# MineralFire-0_4-OLED-inprogress.net
KiCad netlist of a schematic drawn in EAGLE
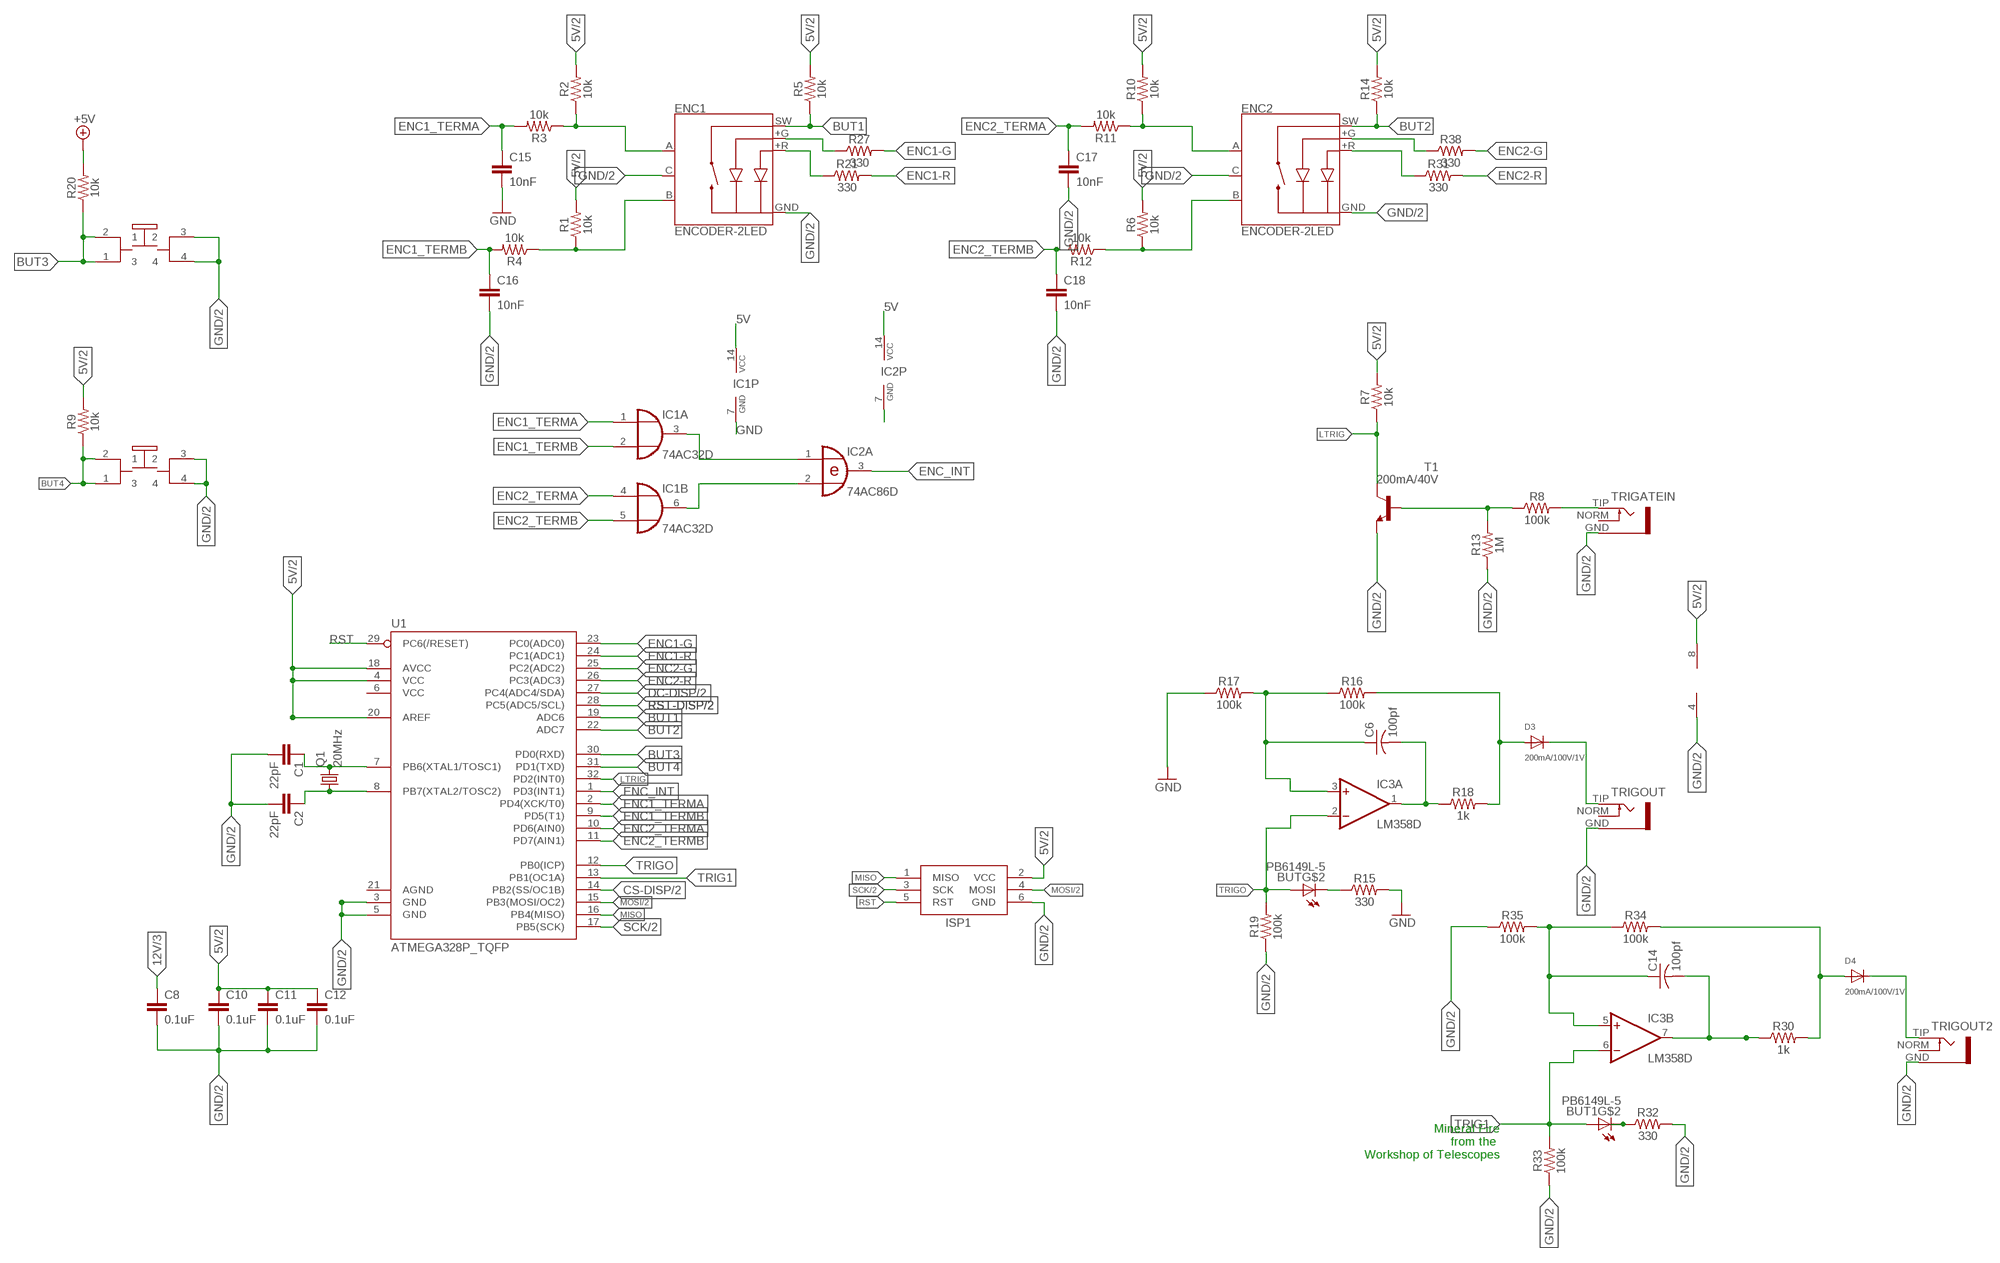
[diagram p0: schematic, sheet 1]
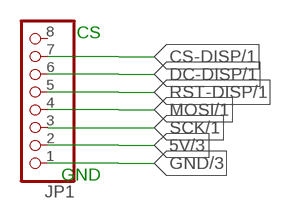
[diagram p1: schematic, sheet 2]
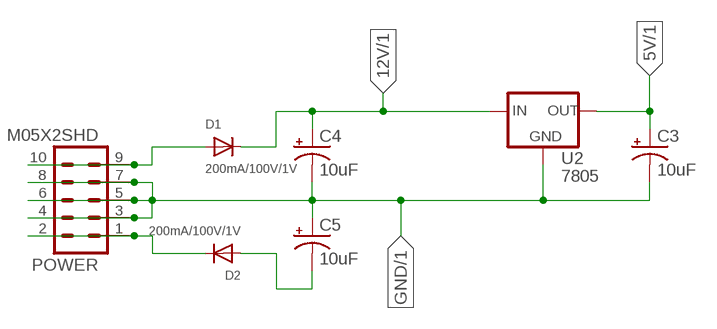
[diagram p2: schematic, sheet 3]

(export (version "E")
  (design (tool "Eeschema 10.0.6"))
  (components
    (comp (ref "BUT")
      (value "PB6149L-5")
      (footprint "eagle-import:PB6149L")
      (libsource (lib "eagle-import") (part "PB6149L-5"))
    )
    (comp (ref "BUT1")
      (value "PB6149L-5")
      (footprint "eagle-import:PB6149L")
      (libsource (lib "eagle-import") (part "PB6149L-5"))
    )
    (comp (ref "C1")
      (value "22pF")
      (footprint "eagle-import:0603")
      (libsource (lib "eagle-import") (part "22PF-0603-50V-5%"))
    )
    (comp (ref "C2")
      (value "22pF")
      (footprint "eagle-import:0603")
      (libsource (lib "eagle-import") (part "22PF-0603-50V-5%"))
    )
    (comp (ref "C6")
      (value "100pf")
      (footprint "eagle-import:C0805K")
      (libsource (lib "eagle-import") (part "C-USC0805K"))
    )
    (comp (ref "C8")
      (value "0.1uF")
      (footprint "eagle-import:0603")
      (libsource (lib "eagle-import") (part "0.1UF-0603-100V-10%"))
    )
    (comp (ref "C10")
      (value "0.1uF")
      (footprint "eagle-import:0603")
      (libsource (lib "eagle-import") (part "0.1UF-0603-100V-10%"))
    )
    (comp (ref "C11")
      (value "0.1uF")
      (footprint "eagle-import:0603")
      (libsource (lib "eagle-import") (part "0.1UF-0603-100V-10%"))
    )
    (comp (ref "C12")
      (value "0.1uF")
      (footprint "eagle-import:0603")
      (libsource (lib "eagle-import") (part "0.1UF-0603-100V-10%"))
    )
    (comp (ref "C14")
      (value "100pf")
      (footprint "eagle-import:C0805K")
      (libsource (lib "eagle-import") (part "C-USC0805K"))
    )
    (comp (ref "C15")
      (value "10nF")
      (footprint "eagle-import:0603")
      (libsource (lib "eagle-import") (part "10NF-0603-50V-10%"))
    )
    (comp (ref "C16")
      (value "10nF")
      (footprint "eagle-import:0603")
      (libsource (lib "eagle-import") (part "10NF-0603-50V-10%"))
    )
    (comp (ref "C17")
      (value "10nF")
      (footprint "eagle-import:0603")
      (libsource (lib "eagle-import") (part "10NF-0603-50V-10%"))
    )
    (comp (ref "C18")
      (value "10nF")
      (footprint "eagle-import:0603")
      (libsource (lib "eagle-import") (part "10NF-0603-50V-10%"))
    )
    (comp (ref "D3")
      (value "200mA/100V/1V")
      (footprint "eagle-import:SMADIODE")
      (libsource (lib "eagle-import") (part "DIODESMA"))
    )
    (comp (ref "D4")
      (value "200mA/100V/1V")
      (footprint "eagle-import:SMADIODE")
      (libsource (lib "eagle-import") (part "DIODESMA"))
    )
    (comp (ref "ENC1")
      (value "ENCODER-2LED")
      (footprint "eagle-import:ENCODER_LED_2")
      (libsource (lib "eagle-import") (part "ENCODER-2LED"))
    )
    (comp (ref "ENC2")
      (value "ENCODER-2LED")
      (footprint "eagle-import:ENCODER_LED_2")
      (libsource (lib "eagle-import") (part "ENCODER-2LED"))
    )
    (comp (ref "IC1")
      (value "74AC32D")
      (footprint "eagle-import:SO14")
      (libsource (lib "eagle-import") (part "7432DAC"))
    )
    (comp (ref "IC2")
      (value "74AC86D")
      (footprint "eagle-import:SO14")
      (libsource (lib "eagle-import") (part "7486DAC"))
    )
    (comp (ref "IC3")
      (value "LM358D")
      (footprint "eagle-import:SO08")
      (libsource (lib "eagle-import") (part "LM358D"))
    )
    (comp (ref "ISP1")
      (value "AVRISP-6")
      (footprint "eagle-import:AVRISP")
      (libsource (lib "eagle-import") (part "AVRISP-6"))
    )
    (comp (ref "Q1")
      (value "20MHz")
      (footprint "eagle-import:HC49UP")
      (libsource (lib "eagle-import") (part "CRYSTALHC49UP"))
    )
    (comp (ref "R1")
      (value "10k")
      (footprint "eagle-import:0603")
      (libsource (lib "eagle-import") (part "10KOHM-0603-1/10W-1%"))
    )
    (comp (ref "R2")
      (value "10k")
      (footprint "eagle-import:0603")
      (libsource (lib "eagle-import") (part "10KOHM-0603-1/10W-1%"))
    )
    (comp (ref "R3")
      (value "10k")
      (footprint "eagle-import:0603")
      (libsource (lib "eagle-import") (part "10KOHM-0603-1/10W-1%"))
    )
    (comp (ref "R4")
      (value "10k")
      (footprint "eagle-import:0603")
      (libsource (lib "eagle-import") (part "10KOHM-0603-1/10W-1%"))
    )
    (comp (ref "R5")
      (value "10k")
      (footprint "eagle-import:0603")
      (libsource (lib "eagle-import") (part "10KOHM-0603-1/10W-1%"))
    )
    (comp (ref "R6")
      (value "10k")
      (footprint "eagle-import:0603")
      (libsource (lib "eagle-import") (part "10KOHM-0603-1/10W-1%"))
    )
    (comp (ref "R7")
      (value "10k")
      (footprint "eagle-import:0603")
      (libsource (lib "eagle-import") (part "10KOHM-0603-1/10W-1%"))
    )
    (comp (ref "R8")
      (value "100k")
      (footprint "eagle-import:0603")
      (libsource (lib "eagle-import") (part "100KOHM-0603-1/10W-1%"))
    )
    (comp (ref "R9")
      (value "10k")
      (footprint "eagle-import:0603")
      (libsource (lib "eagle-import") (part "10KOHM-0603-1/10W-1%"))
    )
    (comp (ref "R10")
      (value "10k")
      (footprint "eagle-import:0603")
      (libsource (lib "eagle-import") (part "10KOHM-0603-1/10W-1%"))
    )
    (comp (ref "R11")
      (value "10k")
      (footprint "eagle-import:0603")
      (libsource (lib "eagle-import") (part "10KOHM-0603-1/10W-1%"))
    )
    (comp (ref "R12")
      (value "10k")
      (footprint "eagle-import:0603")
      (libsource (lib "eagle-import") (part "10KOHM-0603-1/10W-1%"))
    )
    (comp (ref "R13")
      (value "1M")
      (footprint "eagle-import:0603")
      (libsource (lib "eagle-import") (part "1MOHM-0603-1/4W-5%"))
    )
    (comp (ref "R14")
      (value "10k")
      (footprint "eagle-import:0603")
      (libsource (lib "eagle-import") (part "10KOHM-0603-1/10W-1%"))
    )
    (comp (ref "R15")
      (value "330")
      (footprint "eagle-import:0603")
      (libsource (lib "eagle-import") (part "330OHM-0603-1/10W-1%"))
    )
    (comp (ref "R16")
      (value "100k")
      (footprint "eagle-import:0603")
      (libsource (lib "eagle-import") (part "100KOHM-0603-1/10W-1%"))
    )
    (comp (ref "R17")
      (value "100k")
      (footprint "eagle-import:0603")
      (libsource (lib "eagle-import") (part "100KOHM-0603-1/10W-1%"))
    )
    (comp (ref "R18")
      (value "1k")
      (footprint "eagle-import:0603")
      (libsource (lib "eagle-import") (part "1KOHM-0603-1/10W-1%"))
    )
    (comp (ref "R19")
      (value "100k")
      (footprint "eagle-import:0603")
      (libsource (lib "eagle-import") (part "100KOHM-0603-1/10W-1%"))
    )
    (comp (ref "R20")
      (value "10k")
      (footprint "eagle-import:0603")
      (libsource (lib "eagle-import") (part "10KOHM-0603-1/10W-1%"))
    )
    (comp (ref "R21")
      (value "330")
      (footprint "eagle-import:0603")
      (libsource (lib "eagle-import") (part "330OHM-0603-1/10W-1%"))
    )
    (comp (ref "R27")
      (value "330")
      (footprint "eagle-import:0603")
      (libsource (lib "eagle-import") (part "330OHM-0603-1/10W-1%"))
    )
    (comp (ref "R30")
      (value "1k")
      (footprint "eagle-import:0603")
      (libsource (lib "eagle-import") (part "1KOHM-0603-1/10W-1%"))
    )
    (comp (ref "R31")
      (value "330")
      (footprint "eagle-import:0603")
      (libsource (lib "eagle-import") (part "330OHM-0603-1/10W-1%"))
    )
    (comp (ref "R32")
      (value "330")
      (footprint "eagle-import:0603")
      (libsource (lib "eagle-import") (part "330OHM-0603-1/10W-1%"))
    )
    (comp (ref "R33")
      (value "100k")
      (footprint "eagle-import:0603")
      (libsource (lib "eagle-import") (part "100KOHM-0603-1/10W-1%"))
    )
    (comp (ref "R34")
      (value "100k")
      (footprint "eagle-import:0603")
      (libsource (lib "eagle-import") (part "100KOHM-0603-1/10W-1%"))
    )
    (comp (ref "R35")
      (value "100k")
      (footprint "eagle-import:0603")
      (libsource (lib "eagle-import") (part "100KOHM-0603-1/10W-1%"))
    )
    (comp (ref "R38")
      (value "330")
      (footprint "eagle-import:0603")
      (libsource (lib "eagle-import") (part "330OHM-0603-1/10W-1%"))
    )
    (comp (ref "T1")
      (value "200mA/40V")
      (footprint "eagle-import:SOT23-BEC")
      (libsource (lib "eagle-import") (part "-NPN-SOT23-BECMMBT3904LT1"))
    )
    (comp (ref "TRIGATEIN")
      (value "S_JACK")
      (footprint "eagle-import:S_JACK")
      (libsource (lib "eagle-import") (part "S_JACK"))
    )
    (comp (ref "TRIGOUT")
      (value "S_JACK")
      (footprint "eagle-import:S_JACK")
      (libsource (lib "eagle-import") (part "S_JACK"))
    )
    (comp (ref "TRIGOUT2")
      (value "S_JACK")
      (footprint "eagle-import:S_JACK")
      (libsource (lib "eagle-import") (part "S_JACK"))
    )
    (comp (ref "U1")
      (value "ATMEGA328P_TQFP")
      (footprint "eagle-import:TQFP32-08")
      (libsource (lib "eagle-import") (part "ATMEGA328P_TQFP"))
    )
    (comp (ref "JP1")
      (value "MICROBUILDER_HEADER-1X8ROUND")
      (footprint "eagle-import:MICROBUILDER_1X08_ROUND")
      (libsource (lib "eagle-import") (part "MICROBUILDER_HEADER-1X8ROUND"))
    )
    (comp (ref "C3")
      (value "10uF")
      (footprint "eagle-import:153CLV-0505")
      (libsource (lib "eagle-import") (part "CPOL-US153CLV-0505"))
    )
    (comp (ref "C4")
      (value "10uF")
      (footprint "eagle-import:153CLV-0505")
      (libsource (lib "eagle-import") (part "CPOL-US153CLV-0505"))
    )
    (comp (ref "C5")
      (value "10uF")
      (footprint "eagle-import:153CLV-0505")
      (libsource (lib "eagle-import") (part "CPOL-US153CLV-0505"))
    )
    (comp (ref "D1")
      (value "200mA/100V/1V")
      (footprint "eagle-import:SMADIODE")
      (libsource (lib "eagle-import") (part "DIODESMA"))
    )
    (comp (ref "D2")
      (value "200mA/100V/1V")
      (footprint "eagle-import:SMADIODE")
      (libsource (lib "eagle-import") (part "DIODESMA"))
    )
    (comp (ref "POWER")
      (value "M05X2SHD")
      (footprint "eagle-import:2X5-SHROUDED")
      (libsource (lib "eagle-import") (part "M05X2SHD"))
    )
    (comp (ref "U2")
      (value "7805")
      (footprint "eagle-import:V-REG")
      (libsource (lib "eagle-import") (part "V-REG"))
    )
  )
  (nets
    (net (code "1") (name "+5V") (class "Default")
      (node (ref "R20") (pin "2") (pinfunction "2_2") (pintype "passive"))
    )
    (net (code "2") (name "5V") (class "Default")
      (node (ref "C10") (pin "1") (pinfunction "1_1") (pintype "passive"))
      (node (ref "C11") (pin "1") (pinfunction "1_1") (pintype "passive"))
      (node (ref "C12") (pin "1") (pinfunction "1_1") (pintype "passive"))
      (node (ref "C3") (pin "+") (pinfunction "+_+") (pintype "passive"))
      (node (ref "IC1") (pin "14") (pinfunction "VCC_14") (pintype "power_in"))
      (node (ref "IC2") (pin "14") (pinfunction "VCC_14") (pintype "power_in"))
      (node (ref "IC3") (pin "8") (pinfunction "V+_8") (pintype "power_in"))
      (node (ref "ISP1") (pin "2") (pinfunction "VCC_2") (pintype "power_in"))
      (node (ref "JP1") (pin "2") (pinfunction "2_2") (pintype "passive"))
      (node (ref "R1") (pin "2") (pinfunction "2_2") (pintype "passive"))
      (node (ref "R10") (pin "2") (pinfunction "2_2") (pintype "passive"))
      (node (ref "R14") (pin "2") (pinfunction "2_2") (pintype "passive"))
      (node (ref "R2") (pin "2") (pinfunction "2_2") (pintype "passive"))
      (node (ref "R5") (pin "2") (pinfunction "2_2") (pintype "passive"))
      (node (ref "R6") (pin "2") (pinfunction "2_2") (pintype "passive"))
      (node (ref "R7") (pin "2") (pinfunction "2_2") (pintype "passive"))
      (node (ref "R9") (pin "2") (pinfunction "2_2") (pintype "passive"))
      (node (ref "U1") (pin "18") (pinfunction "AVCC_18") (pintype "bidirectional"))
      (node (ref "U1") (pin "20") (pinfunction "AREF_20") (pintype "bidirectional"))
      (node (ref "U1") (pin "4") (pinfunction "VCC_4") (pintype "bidirectional"))
      (node (ref "U2") (pin "3") (pinfunction "OUT_3") (pintype "passive"))
    )
    (net (code "3") (name "12V") (class "Default")
      (node (ref "C4") (pin "+") (pinfunction "+_+") (pintype "passive"))
      (node (ref "C8") (pin "1") (pinfunction "1_1") (pintype "passive"))
      (node (ref "D1") (pin "C") (pinfunction "C_C") (pintype "passive"))
      (node (ref "U2") (pin "1") (pinfunction "IN_1") (pintype "input"))
    )
    (net (code "4") (name "BUT1") (class "Default")
      (node (ref "ENC1") (pin "SW") (pinfunction "SW_SW") (pintype "passive"))
      (node (ref "R5") (pin "1") (pinfunction "1_1") (pintype "passive"))
      (node (ref "U1") (pin "19") (pinfunction "ADC6_19") (pintype "bidirectional"))
    )
    (net (code "5") (name "BUT2") (class "Default")
      (node (ref "ENC2") (pin "SW") (pinfunction "SW_SW") (pintype "passive"))
      (node (ref "R14") (pin "1") (pinfunction "1_1") (pintype "passive"))
      (node (ref "U1") (pin "22") (pinfunction "ADC7_22") (pintype "bidirectional"))
    )
    (net (code "6") (name "BUT3") (class "Default")
      (node (ref "BUT1") (pin "1") (pinfunction "3_1") (pintype "bidirectional"))
      (node (ref "BUT1") (pin "2") (pinfunction "1_2") (pintype "bidirectional"))
      (node (ref "R20") (pin "1") (pinfunction "1_1") (pintype "passive"))
      (node (ref "U1") (pin "30") (pinfunction "PD0(RXD)_30") (pintype "bidirectional"))
    )
    (net (code "7") (name "BUT4") (class "Default")
      (node (ref "BUT") (pin "1") (pinfunction "3_1") (pintype "bidirectional"))
      (node (ref "BUT") (pin "2") (pinfunction "1_2") (pintype "bidirectional"))
      (node (ref "R9") (pin "1") (pinfunction "1_1") (pintype "passive"))
      (node (ref "U1") (pin "31") (pinfunction "PD1(TXD)_31") (pintype "bidirectional"))
    )
    (net (code "8") (name "CS-DISP") (class "Default")
      (node (ref "JP1") (pin "7") (pinfunction "7_7") (pintype "passive"))
      (node (ref "U1") (pin "14") (pinfunction "PB2(SS/OC1B)_14") (pintype "bidirectional"))
    )
    (net (code "9") (name "DC-DISP") (class "Default")
      (node (ref "JP1") (pin "6") (pinfunction "6_6") (pintype "passive"))
      (node (ref "U1") (pin "27") (pinfunction "PC4(ADC4/SDA)_27") (pintype "bidirectional"))
    )
    (net (code "10") (name "ENC1-G") (class "Default")
      (node (ref "R27") (pin "2") (pinfunction "2_2") (pintype "passive"))
      (node (ref "U1") (pin "23") (pinfunction "PC0(ADC0)_23") (pintype "bidirectional"))
    )
    (net (code "11") (name "ENC1-R") (class "Default")
      (node (ref "R21") (pin "2") (pinfunction "2_2") (pintype "passive"))
      (node (ref "U1") (pin "24") (pinfunction "PC1(ADC1)_24") (pintype "bidirectional"))
    )
    (net (code "12") (name "ENC1_TERMA") (class "Default")
      (node (ref "C15") (pin "1") (pinfunction "1_1") (pintype "passive"))
      (node (ref "IC1") (pin "1") (pinfunction "I0_1") (pintype "input"))
      (node (ref "R3") (pin "2") (pinfunction "2_2") (pintype "passive"))
      (node (ref "U1") (pin "2") (pinfunction "PD4(XCK/T0)_2") (pintype "bidirectional"))
    )
    (net (code "13") (name "ENC1_TERMB") (class "Default")
      (node (ref "C16") (pin "1") (pinfunction "1_1") (pintype "passive"))
      (node (ref "IC1") (pin "2") (pinfunction "I1_2") (pintype "input"))
      (node (ref "R4") (pin "2") (pinfunction "2_2") (pintype "passive"))
      (node (ref "U1") (pin "9") (pinfunction "PD5(T1)_9") (pintype "bidirectional"))
    )
    (net (code "14") (name "ENC2-G") (class "Default")
      (node (ref "R38") (pin "2") (pinfunction "2_2") (pintype "passive"))
      (node (ref "U1") (pin "25") (pinfunction "PC2(ADC2)_25") (pintype "bidirectional"))
    )
    (net (code "15") (name "ENC2-R") (class "Default")
      (node (ref "R31") (pin "2") (pinfunction "2_2") (pintype "passive"))
      (node (ref "U1") (pin "26") (pinfunction "PC3(ADC3)_26") (pintype "bidirectional"))
    )
    (net (code "16") (name "ENC2_TERMA") (class "Default")
      (node (ref "C17") (pin "1") (pinfunction "1_1") (pintype "passive"))
      (node (ref "IC1") (pin "4") (pinfunction "I0_4") (pintype "input"))
      (node (ref "R11") (pin "2") (pinfunction "2_2") (pintype "passive"))
      (node (ref "U1") (pin "10") (pinfunction "PD6(AIN0)_10") (pintype "bidirectional"))
    )
    (net (code "17") (name "ENC2_TERMB") (class "Default")
      (node (ref "C18") (pin "1") (pinfunction "1_1") (pintype "passive"))
      (node (ref "IC1") (pin "5") (pinfunction "I1_5") (pintype "input"))
      (node (ref "R12") (pin "2") (pinfunction "2_2") (pintype "passive"))
      (node (ref "U1") (pin "11") (pinfunction "PD7(AIN1)_11") (pintype "bidirectional"))
    )
    (net (code "18") (name "ENC_INT") (class "Default")
      (node (ref "IC2") (pin "3") (pinfunction "O_3") (pintype "output"))
      (node (ref "U1") (pin "1") (pinfunction "PD3(INT1)_1") (pintype "bidirectional"))
    )
    (net (code "19") (name "GND") (class "Default")
      (node (ref "BUT") (pin "3") (pinfunction "2_3") (pintype "bidirectional"))
      (node (ref "BUT") (pin "4") (pinfunction "4_4") (pintype "bidirectional"))
      (node (ref "BUT1") (pin "3") (pinfunction "2_3") (pintype "bidirectional"))
      (node (ref "BUT1") (pin "4") (pinfunction "4_4") (pintype "bidirectional"))
      (node (ref "C1") (pin "2") (pinfunction "2_2") (pintype "passive"))
      (node (ref "C10") (pin "2") (pinfunction "2_2") (pintype "passive"))
      (node (ref "C11") (pin "2") (pinfunction "2_2") (pintype "passive"))
      (node (ref "C12") (pin "2") (pinfunction "2_2") (pintype "passive"))
      (node (ref "C15") (pin "2") (pinfunction "2_2") (pintype "passive"))
      (node (ref "C16") (pin "2") (pinfunction "2_2") (pintype "passive"))
      (node (ref "C17") (pin "2") (pinfunction "2_2") (pintype "passive"))
      (node (ref "C18") (pin "2") (pinfunction "2_2") (pintype "passive"))
      (node (ref "C2") (pin "2") (pinfunction "2_2") (pintype "passive"))
      (node (ref "C3") (pin "-") (pinfunction "-_-") (pintype "passive"))
      (node (ref "C4") (pin "-") (pinfunction "-_-") (pintype "passive"))
      (node (ref "C5") (pin "+") (pinfunction "+_+") (pintype "passive"))
      (node (ref "C8") (pin "2") (pinfunction "2_2") (pintype "passive"))
      (node (ref "ENC1") (pin "C") (pinfunction "C_C") (pintype "bidirectional"))
      (node (ref "ENC1") (pin "GND") (pinfunction "-_GND") (pintype "passive"))
      (node (ref "ENC2") (pin "C") (pinfunction "C_C") (pintype "bidirectional"))
      (node (ref "ENC2") (pin "GND") (pinfunction "-_GND") (pintype "passive"))
      (node (ref "IC1") (pin "7") (pinfunction "GND_7") (pintype "power_in"))
      (node (ref "IC2") (pin "7") (pinfunction "GND_7") (pintype "power_in"))
      (node (ref "IC3") (pin "4") (pinfunction "V-_4") (pintype "power_in"))
      (node (ref "ISP1") (pin "6") (pinfunction "GND_6") (pintype "power_in"))
      (node (ref "JP1") (pin "1") (pinfunction "1_1") (pintype "passive"))
      (node (ref "POWER") (pin "3") (pinfunction "3_3") (pintype "passive"))
      (node (ref "POWER") (pin "4") (pinfunction "4_4") (pintype "passive"))
      (node (ref "POWER") (pin "5") (pinfunction "5_5") (pintype "passive"))
      (node (ref "POWER") (pin "6") (pinfunction "6_6") (pintype "passive"))
      (node (ref "POWER") (pin "7") (pinfunction "7_7") (pintype "passive"))
      (node (ref "POWER") (pin "8") (pinfunction "8_8") (pintype "passive"))
      (node (ref "R13") (pin "1") (pinfunction "1_1") (pintype "passive"))
      (node (ref "R15") (pin "2") (pinfunction "2_2") (pintype "passive"))
      (node (ref "R17") (pin "1") (pinfunction "1_1") (pintype "passive"))
      (node (ref "R19") (pin "1") (pinfunction "1_1") (pintype "passive"))
      (node (ref "R32") (pin "2") (pinfunction "2_2") (pintype "passive"))
      (node (ref "R33") (pin "1") (pinfunction "1_1") (pintype "passive"))
      (node (ref "R35") (pin "1") (pinfunction "1_1") (pintype "passive"))
      (node (ref "T1") (pin "E") (pinfunction "E_E") (pintype "passive"))
      (node (ref "TRIGATEIN") (pin "GND") (pinfunction "GND_GND") (pintype "passive"))
      (node (ref "TRIGOUT") (pin "GND") (pinfunction "GND_GND") (pintype "passive"))
      (node (ref "TRIGOUT2") (pin "GND") (pinfunction "GND_GND") (pintype "passive"))
      (node (ref "U1") (pin "3") (pinfunction "GND_3") (pintype "bidirectional"))
      (node (ref "U1") (pin "5") (pinfunction "GND_5") (pintype "bidirectional"))
      (node (ref "U2") (pin "4") (pinfunction "GND_4") (pintype "input"))
    )
    (net (code "20") (name "LTRIG") (class "Default")
      (node (ref "R7") (pin "1") (pinfunction "1_1") (pintype "passive"))
      (node (ref "T1") (pin "C") (pinfunction "C_C") (pintype "passive"))
      (node (ref "U1") (pin "32") (pinfunction "PD2(INT0)_32") (pintype "bidirectional"))
    )
    (net (code "21") (name "MISO") (class "Default")
      (node (ref "ISP1") (pin "1") (pinfunction "MISO_1") (pintype "input"))
      (node (ref "U1") (pin "16") (pinfunction "PB4(MISO)_16") (pintype "bidirectional"))
    )
    (net (code "22") (name "MOSI") (class "Default")
      (node (ref "ISP1") (pin "4") (pinfunction "MOSI_4") (pintype "output"))
      (node (ref "JP1") (pin "4") (pinfunction "4_4") (pintype "passive"))
      (node (ref "U1") (pin "15") (pinfunction "PB3(MOSI/OC2)_15") (pintype "bidirectional"))
    )
    (net (code "23") (name "Net-(BUT1B-C)") (class "Default")
      (node (ref "BUT1") (pin "K") (pinfunction "C_K") (pintype "passive"))
      (node (ref "R32") (pin "1") (pinfunction "1_1") (pintype "passive"))
    )
    (net (code "24") (name "Net-(BUTB-C)") (class "Default")
      (node (ref "BUT") (pin "K") (pinfunction "C_K") (pintype "passive"))
      (node (ref "R15") (pin "1") (pinfunction "1_1") (pintype "passive"))
    )
    (net (code "25") (name "Net-(C5-Pad-)") (class "Default")
      (node (ref "C5") (pin "-") (pinfunction "-_-") (pintype "passive"))
      (node (ref "D2") (pin "A") (pinfunction "A_A") (pintype "passive"))
    )
    (net (code "26") (name "Net-(D1-PadA)") (class "Default")
      (node (ref "D1") (pin "A") (pinfunction "A_A") (pintype "passive"))
      (node (ref "POWER") (pin "10") (pinfunction "10_10") (pintype "passive"))
      (node (ref "POWER") (pin "9") (pinfunction "9_9") (pintype "passive"))
    )
    (net (code "27") (name "Net-(D2-PadC)") (class "Default")
      (node (ref "D2") (pin "C") (pinfunction "C_C") (pintype "passive"))
      (node (ref "POWER") (pin "1") (pinfunction "1_1") (pintype "passive"))
      (node (ref "POWER") (pin "2") (pinfunction "2_2") (pintype "passive"))
    )
    (net (code "28") (name "Net-(D3-PadA)") (class "Default")
      (node (ref "D3") (pin "A") (pinfunction "A_A") (pintype "passive"))
      (node (ref "R16") (pin "2") (pinfunction "2_2") (pintype "passive"))
      (node (ref "R18") (pin "2") (pinfunction "2_2") (pintype "passive"))
    )
    (net (code "29") (name "Net-(D3-PadC)") (class "Default")
      (node (ref "D3") (pin "C") (pinfunction "C_C") (pintype "passive"))
      (node (ref "TRIGOUT") (pin "TIP") (pinfunction "TIP_TIP") (pintype "passive"))
    )
    (net (code "30") (name "Net-(D4-PadA)") (class "Default")
      (node (ref "D4") (pin "A") (pinfunction "A_A") (pintype "passive"))
      (node (ref "R30") (pin "2") (pinfunction "2_2") (pintype "passive"))
      (node (ref "R34") (pin "2") (pinfunction "2_2") (pintype "passive"))
    )
    (net (code "31") (name "Net-(D4-PadC)") (class "Default")
      (node (ref "D4") (pin "C") (pinfunction "C_C") (pintype "passive"))
      (node (ref "TRIGOUT2") (pin "TIP") (pinfunction "TIP_TIP") (pintype "passive"))
    )
    (net (code "32") (name "Net-(ENC1-Pad+G)") (class "Default")
      (node (ref "ENC1") (pin "+G") (pinfunction "+G_+G") (pintype "passive"))
      (node (ref "R27") (pin "1") (pinfunction "1_1") (pintype "passive"))
    )
    (net (code "33") (name "Net-(ENC1-Pad+R)") (class "Default")
      (node (ref "ENC1") (pin "+R") (pinfunction "+R_+R") (pintype "passive"))
      (node (ref "R21") (pin "1") (pinfunction "1_1") (pintype "passive"))
    )
    (net (code "34") (name "Net-(ENC1-PadA)") (class "Default")
      (node (ref "ENC1") (pin "A") (pinfunction "A_A") (pintype "bidirectional"))
      (node (ref "R2") (pin "1") (pinfunction "1_1") (pintype "passive"))
      (node (ref "R3") (pin "1") (pinfunction "1_1") (pintype "passive"))
    )
    (net (code "35") (name "Net-(ENC1-PadB)") (class "Default")
      (node (ref "ENC1") (pin "B") (pinfunction "B_B") (pintype "bidirectional"))
      (node (ref "R1") (pin "1") (pinfunction "1_1") (pintype "passive"))
      (node (ref "R4") (pin "1") (pinfunction "1_1") (pintype "passive"))
    )
    (net (code "36") (name "Net-(ENC2-Pad+G)") (class "Default")
      (node (ref "ENC2") (pin "+G") (pinfunction "+G_+G") (pintype "passive"))
      (node (ref "R38") (pin "1") (pinfunction "1_1") (pintype "passive"))
    )
    (net (code "37") (name "Net-(ENC2-Pad+R)") (class "Default")
      (node (ref "ENC2") (pin "+R") (pinfunction "+R_+R") (pintype "passive"))
      (node (ref "R31") (pin "1") (pinfunction "1_1") (pintype "passive"))
    )
    (net (code "38") (name "Net-(ENC2-PadA)") (class "Default")
      (node (ref "ENC2") (pin "A") (pinfunction "A_A") (pintype "bidirectional"))
      (node (ref "R10") (pin "1") (pinfunction "1_1") (pintype "passive"))
      (node (ref "R11") (pin "1") (pinfunction "1_1") (pintype "passive"))
    )
    (net (code "39") (name "Net-(ENC2-PadB)") (class "Default")
      (node (ref "ENC2") (pin "B") (pinfunction "B_B") (pintype "bidirectional"))
      (node (ref "R12") (pin "1") (pinfunction "1_1") (pintype "passive"))
      (node (ref "R6") (pin "1") (pinfunction "1_1") (pintype "passive"))
    )
    (net (code "40") (name "Net-(IC1A-O)") (class "Default")
      (node (ref "IC1") (pin "3") (pinfunction "O_3") (pintype "output"))
      (node (ref "IC2") (pin "1") (pinfunction "I0_1") (pintype "input"))
    )
    (net (code "41") (name "Net-(IC1B-O)") (class "Default")
      (node (ref "IC1") (pin "6") (pinfunction "O_6") (pintype "output"))
      (node (ref "IC2") (pin "2") (pinfunction "I1_2") (pintype "input"))
    )
    (net (code "42") (name "Net-(IC3A-+IN)") (class "Default")
      (node (ref "C6") (pin "1") (pinfunction "1_1") (pintype "passive"))
      (node (ref "IC3") (pin "3") (pinfunction "+IN_3") (pintype "input"))
      (node (ref "R16") (pin "1") (pinfunction "1_1") (pintype "passive"))
      (node (ref "R17") (pin "2") (pinfunction "2_2") (pintype "passive"))
    )
    (net (code "43") (name "Net-(IC3A-OUT)") (class "Default")
      (node (ref "C6") (pin "2") (pinfunction "2_2") (pintype "passive"))
      (node (ref "IC3") (pin "1") (pinfunction "OUT_1") (pintype "output"))
      (node (ref "R18") (pin "1") (pinfunction "1_1") (pintype "passive"))
    )
    (net (code "44") (name "Net-(IC3B-+IN)") (class "Default")
      (node (ref "C14") (pin "1") (pinfunction "1_1") (pintype "passive"))
      (node (ref "IC3") (pin "5") (pinfunction "+IN_5") (pintype "input"))
      (node (ref "R34") (pin "1") (pinfunction "1_1") (pintype "passive"))
      (node (ref "R35") (pin "2") (pinfunction "2_2") (pintype "passive"))
    )
    (net (code "45") (name "Net-(IC3B-OUT)") (class "Default")
      (node (ref "C14") (pin "2") (pinfunction "2_2") (pintype "passive"))
      (node (ref "IC3") (pin "7") (pinfunction "OUT_7") (pintype "output"))
      (node (ref "R30") (pin "1") (pinfunction "1_1") (pintype "passive"))
    )
    (net (code "46") (name "Net-(R8-Pad2)") (class "Default")
      (node (ref "R8") (pin "2") (pinfunction "2_2") (pintype "passive"))
      (node (ref "TRIGATEIN") (pin "TIP") (pinfunction "TIP_TIP") (pintype "passive"))
    )
    (net (code "47") (name "Net-(R13-Pad2)") (class "Default")
      (node (ref "R13") (pin "2") (pinfunction "2_2") (pintype "passive"))
      (node (ref "R8") (pin "1") (pinfunction "1_1") (pintype "passive"))
      (node (ref "T1") (pin "B") (pinfunction "B_B") (pintype "passive"))
    )
    (net (code "48") (name "Net-(U1-PB6(XTAL1{slash}TOSC1))") (class "Default")
      (node (ref "C1") (pin "1") (pinfunction "1_1") (pintype "passive"))
      (node (ref "Q1") (pin "2") (pinfunction "2_2") (pintype "passive"))
      (node (ref "U1") (pin "7") (pinfunction "PB6(XTAL1/TOSC1)_7") (pintype "bidirectional"))
    )
    (net (code "49") (name "Net-(U1-PB7(XTAL2{slash}TOSC2))") (class "Default")
      (node (ref "C2") (pin "1") (pinfunction "1_1") (pintype "passive"))
      (node (ref "Q1") (pin "1") (pinfunction "1_1") (pintype "passive"))
      (node (ref "U1") (pin "8") (pinfunction "PB7(XTAL2/TOSC2)_8") (pintype "bidirectional"))
    )
    (net (code "50") (name "RST") (class "Default")
      (node (ref "ISP1") (pin "5") (pinfunction "RST_5") (pintype "output"))
      (node (ref "U1") (pin "29") (pinfunction "PC6(/RESET)_29") (pintype "bidirectional"))
    )
    (net (code "51") (name "RST-DISP") (class "Default")
      (node (ref "JP1") (pin "5") (pinfunction "5_5") (pintype "passive"))
      (node (ref "U1") (pin "28") (pinfunction "PC5(ADC5/SCL)_28") (pintype "bidirectional"))
    )
    (net (code "52") (name "SCK") (class "Default")
      (node (ref "ISP1") (pin "3") (pinfunction "SCK_3") (pintype "output"))
      (node (ref "JP1") (pin "3") (pinfunction "3_3") (pintype "passive"))
      (node (ref "U1") (pin "17") (pinfunction "PB5(SCK)_17") (pintype "bidirectional"))
    )
    (net (code "53") (name "TRIG1") (class "Default")
      (node (ref "BUT1") (pin "A") (pinfunction "A_A") (pintype "passive"))
      (node (ref "IC3") (pin "6") (pinfunction "-IN_6") (pintype "input"))
      (node (ref "R33") (pin "2") (pinfunction "2_2") (pintype "passive"))
      (node (ref "U1") (pin "13") (pinfunction "PB1(OC1A)_13") (pintype "bidirectional"))
    )
    (net (code "54") (name "TRIGO") (class "Default")
      (node (ref "BUT") (pin "A") (pinfunction "A_A") (pintype "passive"))
      (node (ref "IC3") (pin "2") (pinfunction "-IN_2") (pintype "input"))
      (node (ref "R19") (pin "2") (pinfunction "2_2") (pintype "passive"))
      (node (ref "U1") (pin "12") (pinfunction "PB0(ICP)_12") (pintype "bidirectional"))
    )
    (net (code "55") (name "unconnected-(JP1-Pad8)") (class "Default")
      (node (ref "JP1") (pin "8") (pinfunction "8_8") (pintype "passive"))
    )
    (net (code "56") (name "unconnected-(TRIGATEIN-PadNORM)") (class "Default")
      (node (ref "TRIGATEIN") (pin "NORM") (pinfunction "NORM_NORM") (pintype "passive"))
    )
    (net (code "57") (name "unconnected-(TRIGOUT-PadNORM)") (class "Default")
      (node (ref "TRIGOUT") (pin "NORM") (pinfunction "NORM_NORM") (pintype "passive"))
    )
    (net (code "58") (name "unconnected-(TRIGOUT2-PadNORM)") (class "Default")
      (node (ref "TRIGOUT2") (pin "NORM") (pinfunction "NORM_NORM") (pintype "passive"))
    )
    (net (code "59") (name "unconnected-(U1-AGND-Pad21)") (class "Default")
      (node (ref "U1") (pin "21") (pinfunction "AGND_21") (pintype "bidirectional"))
    )
    (net (code "60") (name "unconnected-(U1-VCC-Pad6)") (class "Default")
      (node (ref "U1") (pin "6") (pinfunction "VCC_6") (pintype "bidirectional"))
    )
  )
)
